# card.net
KiCad netlist of a schematic drawn in EAGLE
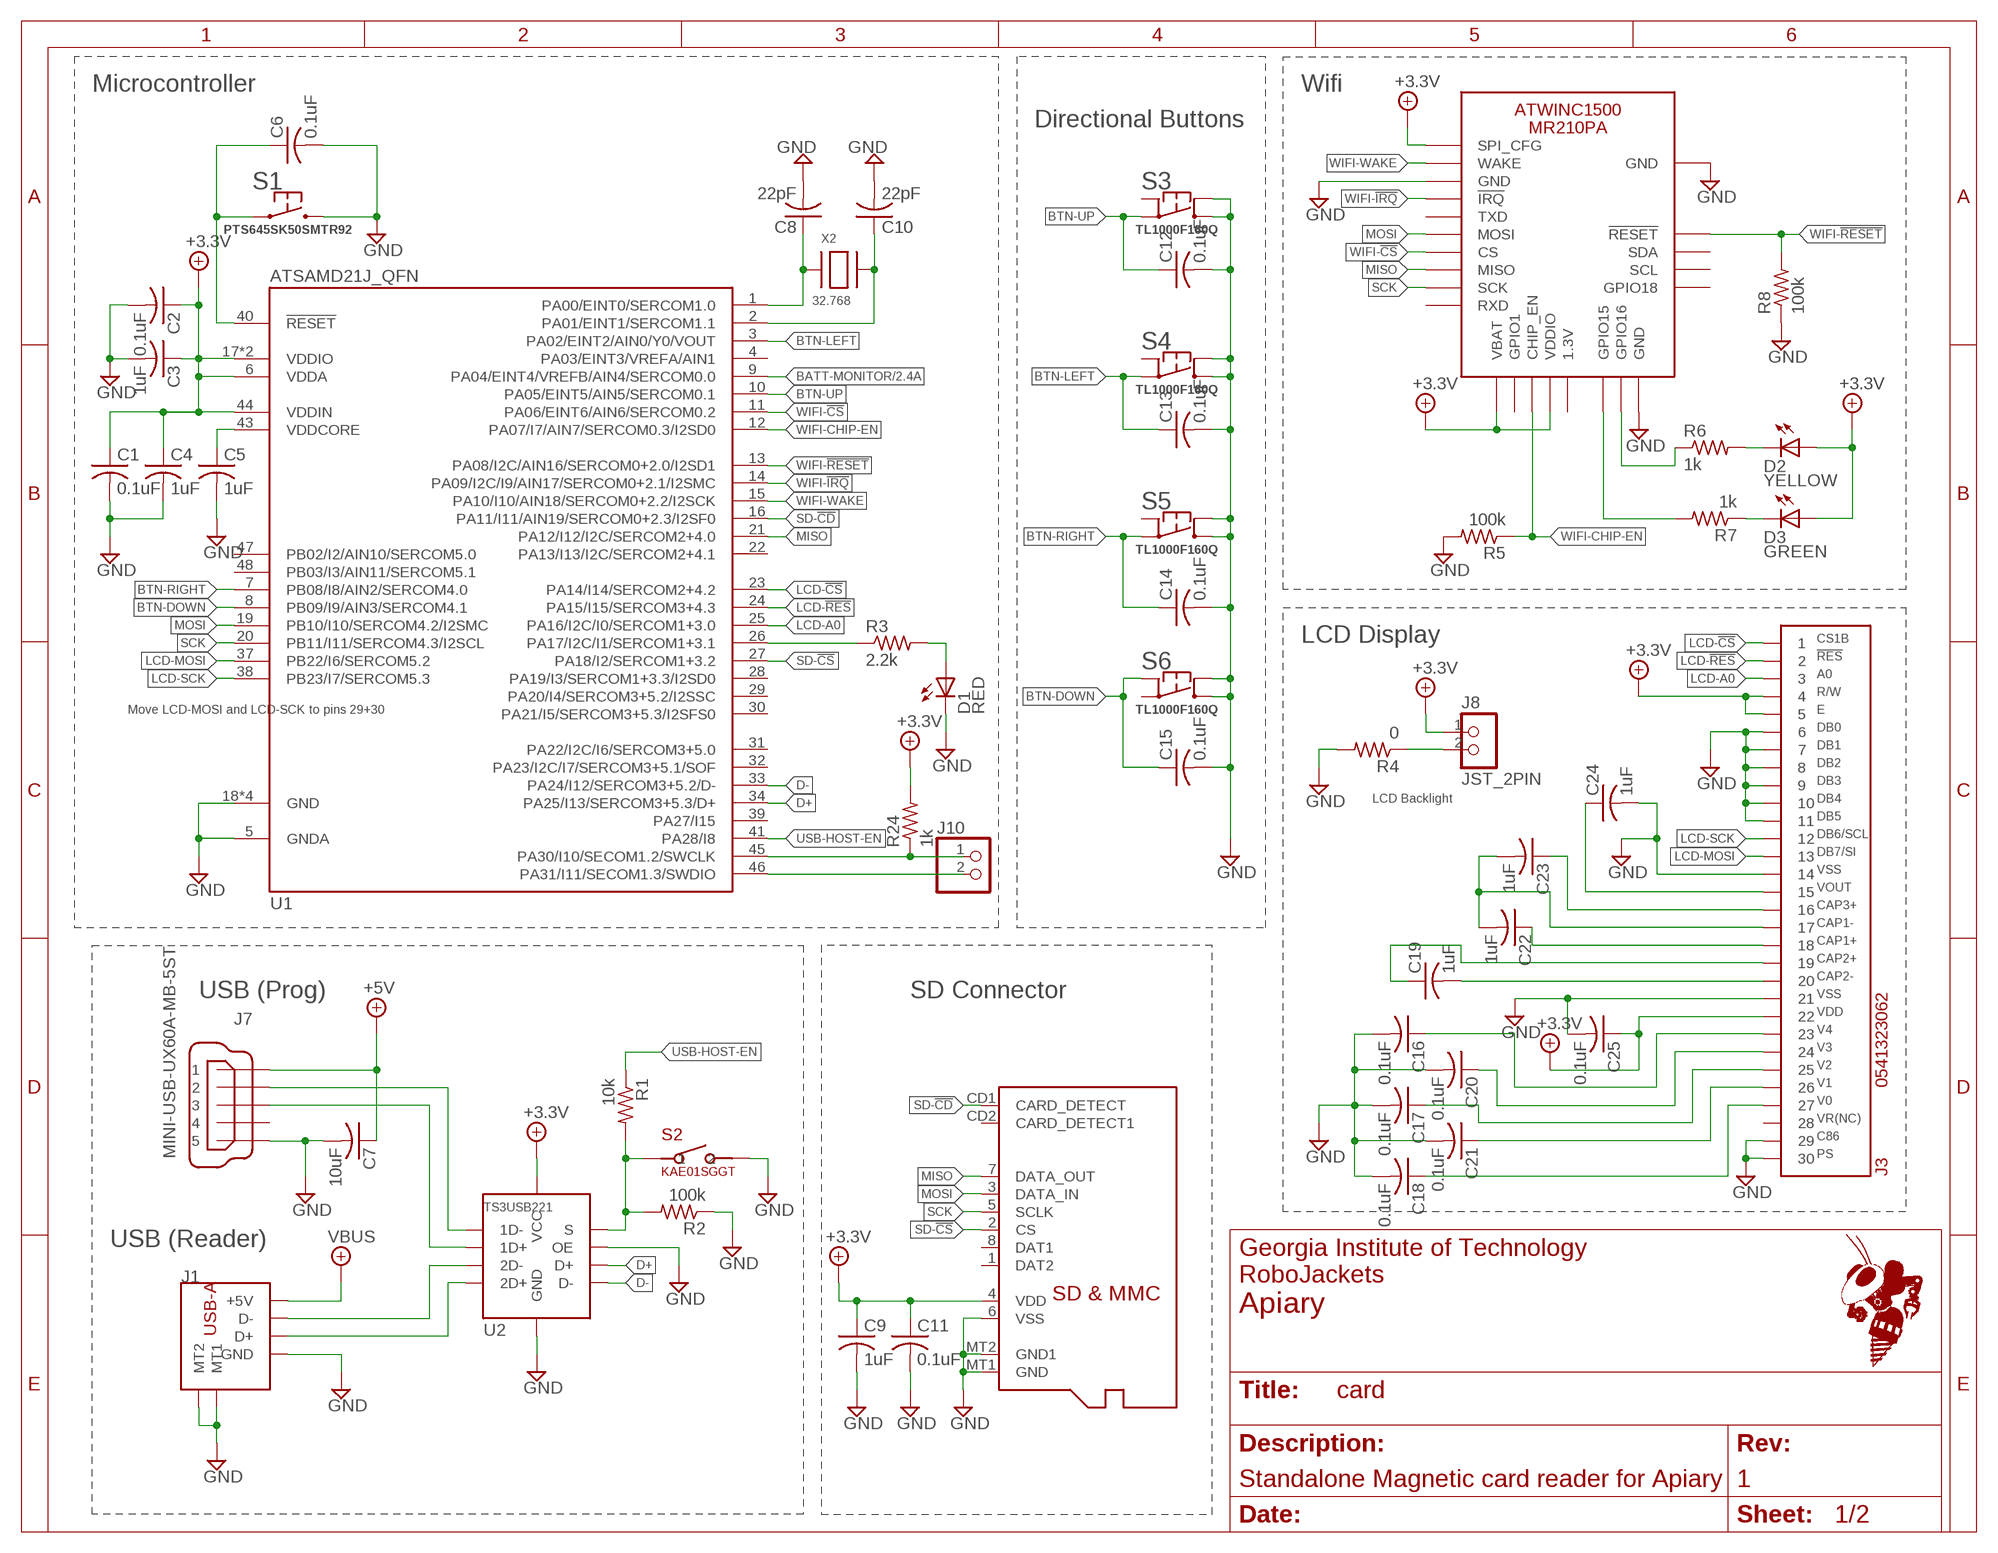
[diagram p0: schematic, sheet 1]
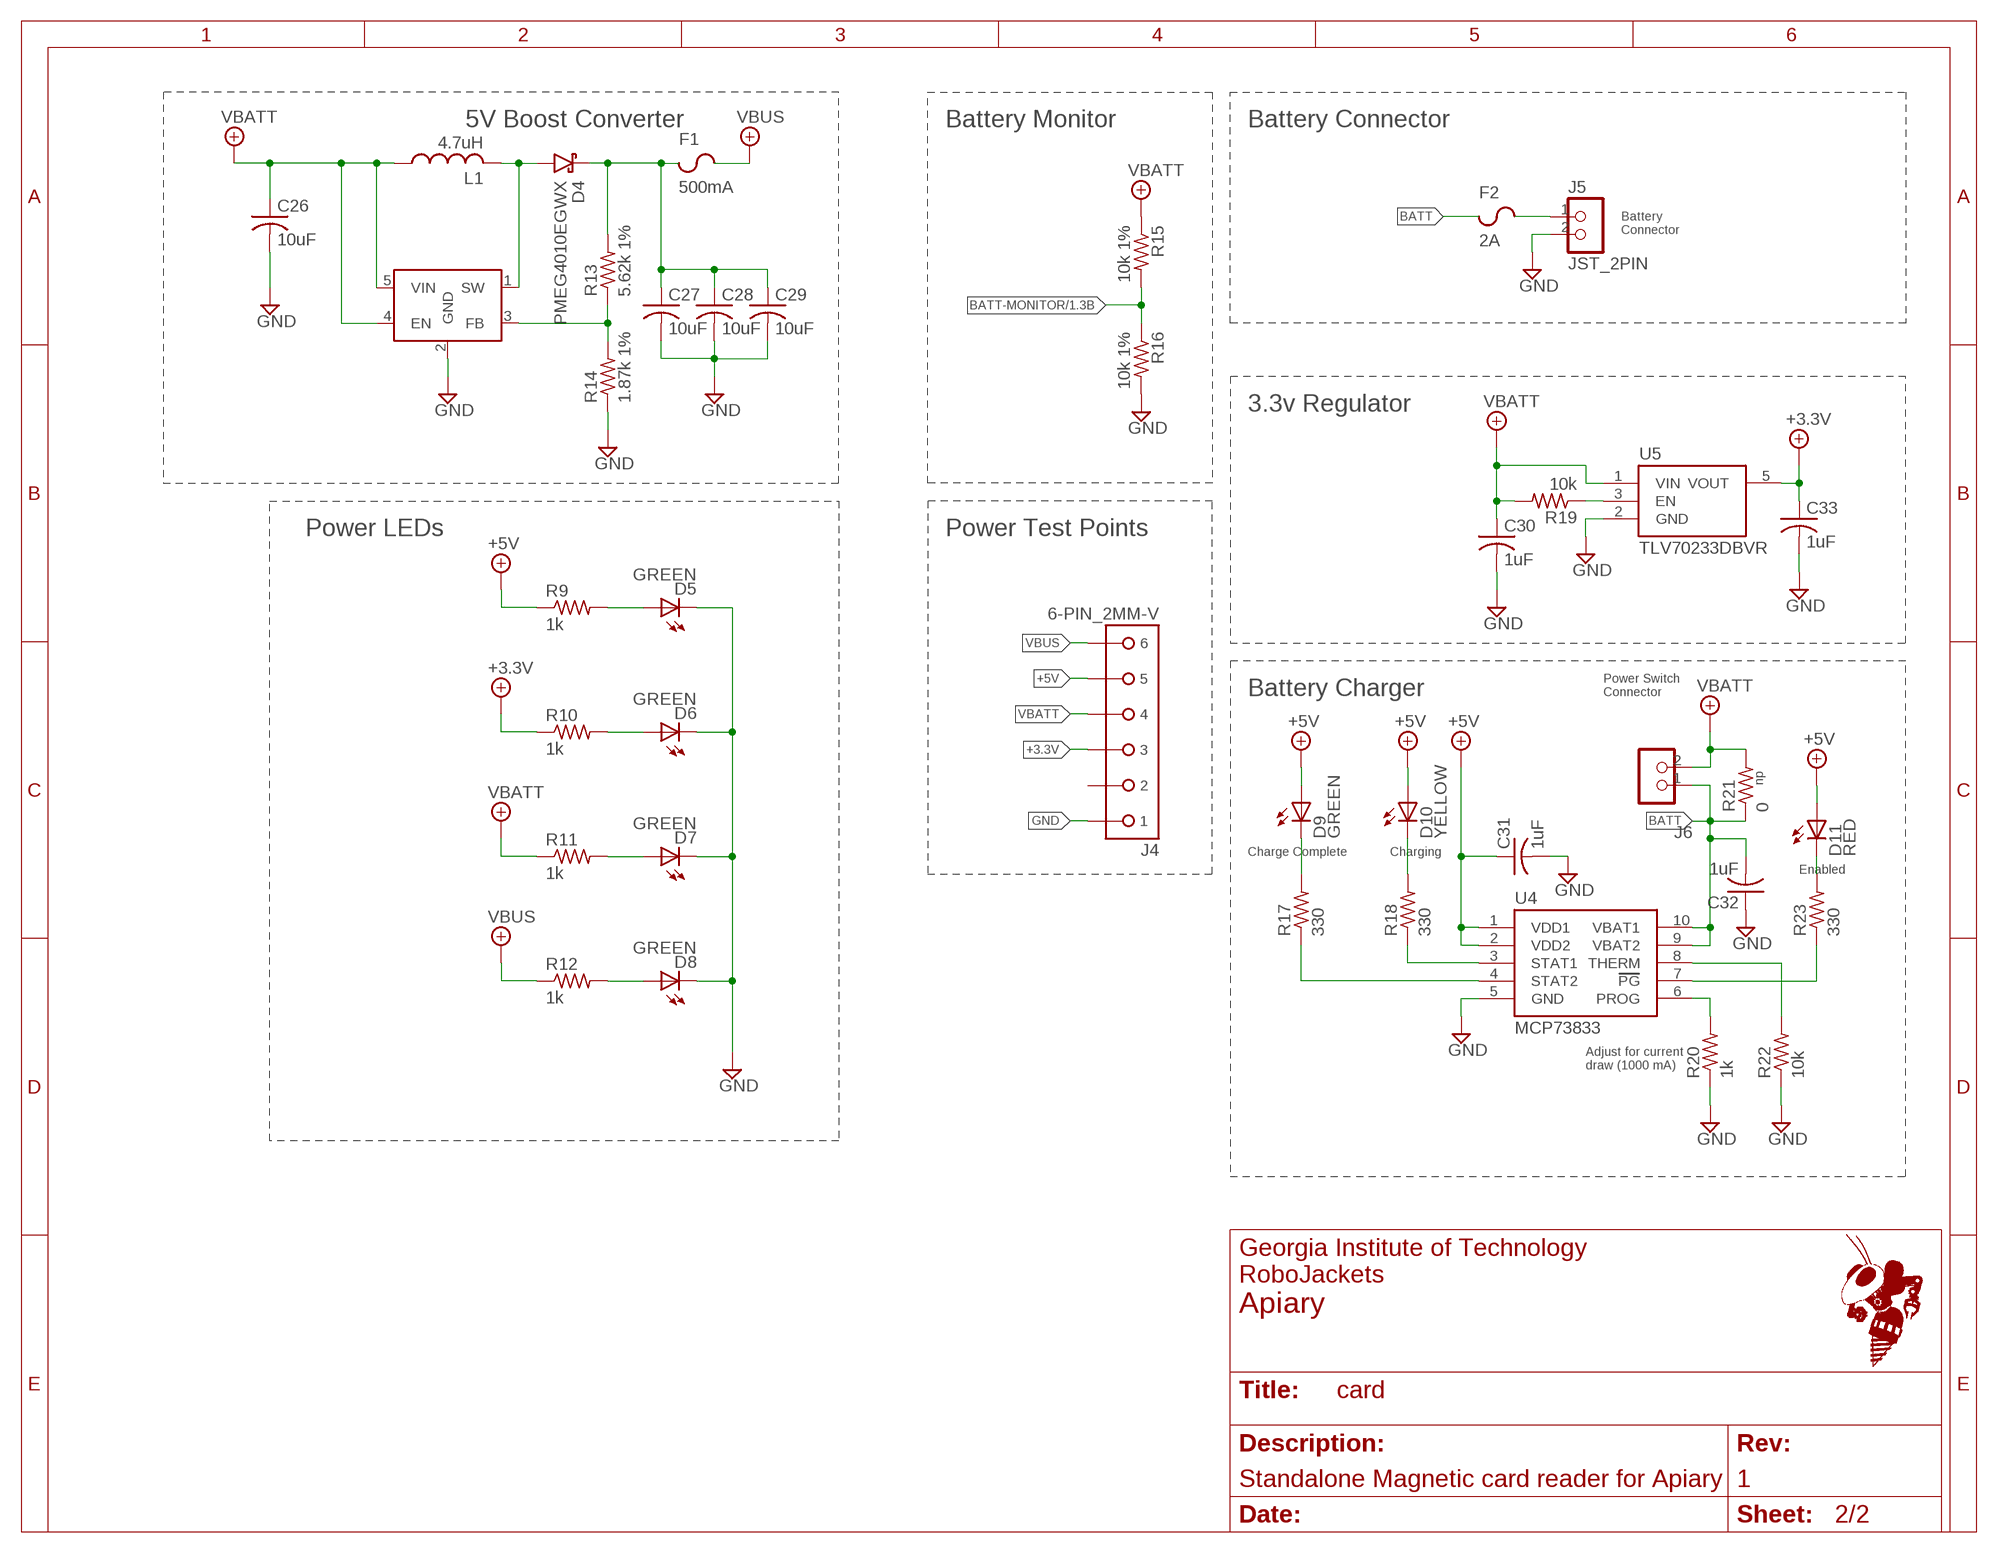
[diagram p1: schematic, sheet 2]

(export (version "E")
  (design (tool "Eeschema 10.0.6"))
  (components
    (comp (ref "C1")
      (value "0.1uF")
      (footprint "eagle-import:C0603")
      (libsource (lib "eagle-import") (part "rcl_334_C-USC0603"))
    )
    (comp (ref "C2")
      (value "0.1uF")
      (footprint "eagle-import:C0603")
      (libsource (lib "eagle-import") (part "rcl_334_C-USC0603"))
    )
    (comp (ref "C3")
      (value "1uF")
      (footprint "eagle-import:C0603")
      (libsource (lib "eagle-import") (part "rcl_334_C-USC0603"))
    )
    (comp (ref "C4")
      (value "1uF")
      (footprint "eagle-import:C0603")
      (libsource (lib "eagle-import") (part "rcl_334_C-USC0603"))
    )
    (comp (ref "C5")
      (value "1uF")
      (footprint "eagle-import:C0603")
      (libsource (lib "eagle-import") (part "rcl_334_C-USC0603"))
    )
    (comp (ref "C6")
      (value "0.1uF")
      (footprint "eagle-import:C0603")
      (libsource (lib "eagle-import") (part "rcl_334_C-USC0603"))
    )
    (comp (ref "C7")
      (value "10uF")
      (footprint "eagle-import:C0603")
      (libsource (lib "eagle-import") (part "C-USC0603"))
    )
    (comp (ref "C8")
      (value "22pF")
      (footprint "eagle-import:C0603")
      (libsource (lib "eagle-import") (part "rcl_334_C-USC0603"))
    )
    (comp (ref "C9")
      (value "1uF")
      (footprint "eagle-import:C0603")
      (libsource (lib "eagle-import") (part "rcl_334_C-USC0603"))
    )
    (comp (ref "C10")
      (value "22pF")
      (footprint "eagle-import:C0603")
      (libsource (lib "eagle-import") (part "rcl_334_C-USC0603"))
    )
    (comp (ref "C11")
      (value "0.1uF")
      (footprint "eagle-import:C0603")
      (libsource (lib "eagle-import") (part "rcl_334_C-USC0603"))
    )
    (comp (ref "C12")
      (value "0.1uF")
      (footprint "eagle-import:C0603")
      (libsource (lib "eagle-import") (part "rcl_334_C-USC0603"))
    )
    (comp (ref "C13")
      (value "0.1uF")
      (footprint "eagle-import:C0603")
      (libsource (lib "eagle-import") (part "rcl_334_C-USC0603"))
    )
    (comp (ref "C14")
      (value "0.1uF")
      (footprint "eagle-import:C0603")
      (libsource (lib "eagle-import") (part "rcl_334_C-USC0603"))
    )
    (comp (ref "C15")
      (value "0.1uF")
      (footprint "eagle-import:C0603")
      (libsource (lib "eagle-import") (part "rcl_334_C-USC0603"))
    )
    (comp (ref "C16")
      (value "0.1uF")
      (footprint "eagle-import:C0603")
      (libsource (lib "eagle-import") (part "rcl_334_C-USC0603"))
    )
    (comp (ref "C17")
      (value "0.1uF")
      (footprint "eagle-import:C0603")
      (libsource (lib "eagle-import") (part "rcl_334_C-USC0603"))
    )
    (comp (ref "C18")
      (value "0.1uF")
      (footprint "eagle-import:C0603")
      (libsource (lib "eagle-import") (part "rcl_334_C-USC0603"))
    )
    (comp (ref "C19")
      (value "1uF")
      (footprint "eagle-import:C0603")
      (libsource (lib "eagle-import") (part "rcl_334_C-USC0603"))
    )
    (comp (ref "C20")
      (value "0.1uF")
      (footprint "eagle-import:C0603")
      (libsource (lib "eagle-import") (part "rcl_334_C-USC0603"))
    )
    (comp (ref "C21")
      (value "0.1uF")
      (footprint "eagle-import:C0603")
      (libsource (lib "eagle-import") (part "rcl_334_C-USC0603"))
    )
    (comp (ref "C22")
      (value "1uF")
      (footprint "eagle-import:C0603")
      (libsource (lib "eagle-import") (part "rcl_334_C-USC0603"))
    )
    (comp (ref "C23")
      (value "1uF")
      (footprint "eagle-import:C0603")
      (libsource (lib "eagle-import") (part "rcl_334_C-USC0603"))
    )
    (comp (ref "C24")
      (value "1uF")
      (footprint "eagle-import:C0603")
      (libsource (lib "eagle-import") (part "rcl_334_C-USC0603"))
    )
    (comp (ref "C25")
      (value "0.1uF")
      (footprint "eagle-import:C0603")
      (libsource (lib "eagle-import") (part "rcl_334_C-USC0603"))
    )
    (comp (ref "D1")
      (value "RED")
      (footprint "eagle-import:CHIP-LED0603")
      (fields (field (name "MPN") "LTST-C191KRKT"))
      (libsource (lib "eagle-import") (part "LED-SMD-RED"))
    )
    (comp (ref "D2")
      (value "YELLOW")
      (footprint "eagle-import:CHIP-LED0603")
      (fields (field (name "MPN") "LTST-C191KSKT"))
      (libsource (lib "eagle-import") (part "LED-SMD-YELLOW"))
    )
    (comp (ref "D3")
      (value "GREEN")
      (footprint "eagle-import:CHIP-LED0603")
      (fields (field (name "MPN") "LTST-C191KGKT"))
      (libsource (lib "eagle-import") (part "LED-SMD-GREEN"))
    )
    (comp (ref "J1")
      (value "UE27AC54100")
      (footprint "eagle-import:USB-A")
      (libsource (lib "eagle-import") (part "UE27AC54100"))
    )
    (comp (ref "J2")
      (value "MICROSD")
      (footprint "eagle-import:MICROSD")
      (libsource (lib "eagle-import") (part "MICROSD"))
    )
    (comp (ref "J3")
      (value "0541323062")
      (footprint "eagle-import:0541323062")
      (libsource (lib "eagle-import") (part "0541323062"))
    )
    (comp (ref "J7")
      (value "MINI-USB-UX60A-MB-5ST")
      (footprint "eagle-import:UX60A-MB-5ST")
      (libsource (lib "eagle-import") (part "MINI-USB-UX60A-MB-5ST"))
    )
    (comp (ref "J8")
      (value "JST_2PIN")
      (footprint "eagle-import:JSTPH2")
      (libsource (lib "eagle-import") (part "card_JST_2PIN"))
    )
    (comp (ref "J10")
      (value "CONN-2VERT")
      (footprint "eagle-import:1X2")
      (libsource (lib "eagle-import") (part "CONN-2VERT"))
    )
    (comp (ref "R1")
      (value "10k")
      (footprint "eagle-import:R0603")
      (libsource (lib "eagle-import") (part "R-US_R0603"))
    )
    (comp (ref "R2")
      (value "100k")
      (footprint "eagle-import:R0603")
      (libsource (lib "eagle-import") (part "R-US_R0603"))
    )
    (comp (ref "R3")
      (value "2.2k")
      (footprint "eagle-import:R0603")
      (libsource (lib "eagle-import") (part "R-US_R0603"))
    )
    (comp (ref "R4")
      (value "0")
      (footprint "eagle-import:R0603")
      (libsource (lib "eagle-import") (part "R-US_R0603"))
    )
    (comp (ref "R5")
      (value "100k")
      (footprint "eagle-import:R0603")
      (libsource (lib "eagle-import") (part "R-US_R0603"))
    )
    (comp (ref "R6")
      (value "1k")
      (footprint "eagle-import:R0603")
      (libsource (lib "eagle-import") (part "R-US_R0603"))
    )
    (comp (ref "R7")
      (value "1k")
      (footprint "eagle-import:R0603")
      (libsource (lib "eagle-import") (part "R-US_R0603"))
    )
    (comp (ref "R8")
      (value "100k")
      (footprint "eagle-import:R0603")
      (libsource (lib "eagle-import") (part "R-US_R0603"))
    )
    (comp (ref "R24")
      (value "1k")
      (footprint "eagle-import:R0603")
      (libsource (lib "eagle-import") (part "R-US_R0603"))
    )
    (comp (ref "S1")
      (value "PTS645SK50SMTR92")
      (footprint "eagle-import:PTS645SK50SMTR92")
      (libsource (lib "eagle-import") (part "PTS645SK50SMTR92"))
    )
    (comp (ref "S2")
      (value "KAE01SGGT")
      (footprint "eagle-import:KAE01SGGT")
      (libsource (lib "eagle-import") (part "KAE01SGGT"))
    )
    (comp (ref "S3")
      (value "TL1000F160Q")
      (footprint "eagle-import:TL1100")
      (libsource (lib "eagle-import") (part "TL1000F160Q"))
    )
    (comp (ref "S4")
      (value "TL1000F160Q")
      (footprint "eagle-import:TL1100")
      (libsource (lib "eagle-import") (part "TL1000F160Q"))
    )
    (comp (ref "S5")
      (value "TL1000F160Q")
      (footprint "eagle-import:TL1100")
      (libsource (lib "eagle-import") (part "TL1000F160Q"))
    )
    (comp (ref "S6")
      (value "TL1000F160Q")
      (footprint "eagle-import:TL1100")
      (libsource (lib "eagle-import") (part "TL1000F160Q"))
    )
    (comp (ref "U1")
      (value "ATSAMD21J_QFN")
      (footprint "eagle-import:TQFN48_7MM")
      (libsource (lib "eagle-import") (part "ATSAMD21J_QFN"))
    )
    (comp (ref "U2")
      (value "TS3USB221")
      (footprint "eagle-import:10-PIN-UQFN")
      (libsource (lib "eagle-import") (part "TS3USB221"))
    )
    (comp (ref "X2")
      (value "32.768")
      (footprint "eagle-import:XTAL3215")
      (libsource (lib "eagle-import") (part "XTAL-3.2X1.5"))
    )
    (comp (ref "X3")
      (value "ATWINC1500_MR210PA")
      (footprint "eagle-import:ATWINC1500_MR210PA")
      (libsource (lib "eagle-import") (part "ATWINC1500_MR210PA"))
    )
    (comp (ref "C26")
      (value "10uF")
      (footprint "eagle-import:C0603")
      (libsource (lib "eagle-import") (part "rcl_334_C-USC0603"))
    )
    (comp (ref "C27")
      (value "10uF")
      (footprint "eagle-import:C0603")
      (libsource (lib "eagle-import") (part "rcl_334_C-USC0603"))
    )
    (comp (ref "C28")
      (value "10uF")
      (footprint "eagle-import:C0603")
      (libsource (lib "eagle-import") (part "rcl_334_C-USC0603"))
    )
    (comp (ref "C29")
      (value "10uF")
      (footprint "eagle-import:C0603")
      (libsource (lib "eagle-import") (part "rcl_334_C-USC0603"))
    )
    (comp (ref "C30")
      (value "1uF")
      (footprint "eagle-import:C0603")
      (libsource (lib "eagle-import") (part "rcl_334_C-USC0603"))
    )
    (comp (ref "C31")
      (value "1uF")
      (footprint "eagle-import:C0603")
      (libsource (lib "eagle-import") (part "rcl_334_C-USC0603"))
    )
    (comp (ref "C32")
      (value "1uF")
      (footprint "eagle-import:C0603")
      (libsource (lib "eagle-import") (part "rcl_334_C-USC0603"))
    )
    (comp (ref "C33")
      (value "1uF")
      (footprint "eagle-import:C0603")
      (libsource (lib "eagle-import") (part "rcl_334_C-USC0603"))
    )
    (comp (ref "D4")
      (value "PMEG4010EGWX")
      (footprint "eagle-import:SOD123")
      (libsource (lib "eagle-import") (part "SCHOTTKEY-DIODE-SOD123"))
    )
    (comp (ref "D5")
      (value "GREEN")
      (footprint "eagle-import:CHIP-LED0603")
      (fields (field (name "MPN") "LTST-C191KGKT"))
      (libsource (lib "eagle-import") (part "LED-SMD-GREEN"))
    )
    (comp (ref "D6")
      (value "GREEN")
      (footprint "eagle-import:CHIP-LED0603")
      (fields (field (name "MPN") "LTST-C191KGKT"))
      (libsource (lib "eagle-import") (part "LED-SMD-GREEN"))
    )
    (comp (ref "D7")
      (value "GREEN")
      (footprint "eagle-import:CHIP-LED0603")
      (fields (field (name "MPN") "LTST-C191KGKT"))
      (libsource (lib "eagle-import") (part "LED-SMD-GREEN"))
    )
    (comp (ref "D8")
      (value "GREEN")
      (footprint "eagle-import:CHIP-LED0603")
      (fields (field (name "MPN") "LTST-C191KGKT"))
      (libsource (lib "eagle-import") (part "LED-SMD-GREEN"))
    )
    (comp (ref "D9")
      (value "GREEN")
      (footprint "eagle-import:CHIP-LED0603")
      (fields (field (name "MPN") "LTST-C191KGKT"))
      (libsource (lib "eagle-import") (part "LED-SMD-GREEN"))
    )
    (comp (ref "D10")
      (value "YELLOW")
      (footprint "eagle-import:CHIP-LED0603")
      (fields (field (name "MPN") "LTST-C191KSKT"))
      (libsource (lib "eagle-import") (part "LED-SMD-YELLOW"))
    )
    (comp (ref "D11")
      (value "RED")
      (footprint "eagle-import:CHIP-LED0603")
      (fields (field (name "MPN") "LTST-C191KRKT"))
      (libsource (lib "eagle-import") (part "LED-SMD-RED"))
    )
    (comp (ref "F1")
      (value "500mA")
      (footprint "eagle-import:F0603")
      (libsource (lib "eagle-import") (part "CHIP_FUSE0603"))
    )
    (comp (ref "F2")
      (value "2A")
      (footprint "eagle-import:F0603")
      (libsource (lib "eagle-import") (part "CHIP_FUSE0603"))
    )
    (comp (ref "J4")
      (value "6-PIN_2MM-V")
      (footprint "eagle-import:2MM-6-V")
      (libsource (lib "eagle-import") (part "6-PIN_2MM-V"))
    )
    (comp (ref "J5")
      (value "JST_2PIN")
      (footprint "eagle-import:JSTPH2")
      (libsource (lib "eagle-import") (part "JST_2PIN"))
    )
    (comp (ref "J6")
      (value "JST_2PIN")
      (footprint "eagle-import:JSTPH2")
      (libsource (lib "eagle-import") (part "JST_2PIN"))
    )
    (comp (ref "L1")
      (value "4.7uH")
      (footprint "eagle-import:L0805")
      (libsource (lib "eagle-import") (part "L-US-0805"))
    )
    (comp (ref "R9")
      (value "1k")
      (footprint "eagle-import:R0603")
      (libsource (lib "eagle-import") (part "R-US_R0603"))
    )
    (comp (ref "R10")
      (value "1k")
      (footprint "eagle-import:R0603")
      (libsource (lib "eagle-import") (part "R-US_R0603"))
    )
    (comp (ref "R11")
      (value "1k")
      (footprint "eagle-import:R0603")
      (libsource (lib "eagle-import") (part "R-US_R0603"))
    )
    (comp (ref "R12")
      (value "1k")
      (footprint "eagle-import:R0603")
      (libsource (lib "eagle-import") (part "R-US_R0603"))
    )
    (comp (ref "R13")
      (value "5.62k 1%")
      (footprint "eagle-import:R0603")
      (libsource (lib "eagle-import") (part "R-US_R0603"))
    )
    (comp (ref "R14")
      (value "1.87k 1%")
      (footprint "eagle-import:R0603")
      (libsource (lib "eagle-import") (part "R-US_R0603"))
    )
    (comp (ref "R15")
      (value "10k 1%")
      (footprint "eagle-import:R0603")
      (libsource (lib "eagle-import") (part "R-US_R0603"))
    )
    (comp (ref "R16")
      (value "10k 1%")
      (footprint "eagle-import:R0603")
      (libsource (lib "eagle-import") (part "R-US_R0603"))
    )
    (comp (ref "R17")
      (value "330")
      (footprint "eagle-import:R0603")
      (libsource (lib "eagle-import") (part "R-US_R0603"))
    )
    (comp (ref "R18")
      (value "330")
      (footprint "eagle-import:R0603")
      (libsource (lib "eagle-import") (part "R-US_R0603"))
    )
    (comp (ref "R19")
      (value "10k")
      (footprint "eagle-import:R0603")
      (libsource (lib "eagle-import") (part "R-US_R0603"))
    )
    (comp (ref "R20")
      (value "1k")
      (footprint "eagle-import:R0603")
      (libsource (lib "eagle-import") (part "R-US_R0603"))
    )
    (comp (ref "R21")
      (value "0")
      (footprint "eagle-import:R0603")
      (libsource (lib "eagle-import") (part "R-US_R0603"))
    )
    (comp (ref "R22")
      (value "10k")
      (footprint "eagle-import:R0603")
      (libsource (lib "eagle-import") (part "R-US_R0603"))
    )
    (comp (ref "R23")
      (value "330")
      (footprint "eagle-import:R0603")
      (libsource (lib "eagle-import") (part "R-US_R0603"))
    )
    (comp (ref "U3")
      (value "MIC2288YD5-TR")
      (footprint "eagle-import:TSOT-23-5")
      (libsource (lib "eagle-import") (part "MIC2288YD5-TR"))
    )
    (comp (ref "U4")
      (value "MCP73833")
      (footprint "eagle-import:MSOP10")
      (libsource (lib "eagle-import") (part "MCP73833"))
    )
    (comp (ref "U5")
      (value "TLV70233DBVR")
      (footprint "eagle-import:SOT-23-5")
      (libsource (lib "eagle-import") (part "TLV70233DBVR"))
    )
  )
  (nets
    (net (code "1") (name "+3.3V") (class "Default")
      (node (ref "C1") (pin "1") (pinfunction "1_1") (pintype "passive"))
      (node (ref "C11") (pin "1") (pinfunction "1_1") (pintype "passive"))
      (node (ref "C2") (pin "1") (pinfunction "1_1") (pintype "passive"))
      (node (ref "C25") (pin "1") (pinfunction "1_1") (pintype "passive"))
      (node (ref "C3") (pin "1") (pinfunction "1_1") (pintype "passive"))
      (node (ref "C33") (pin "1") (pinfunction "1_1") (pintype "passive"))
      (node (ref "C4") (pin "1") (pinfunction "1_1") (pintype "passive"))
      (node (ref "C9") (pin "1") (pinfunction "1_1") (pintype "passive"))
      (node (ref "D2") (pin "A") (pinfunction "A_A") (pintype "passive"))
      (node (ref "D3") (pin "A") (pinfunction "A_A") (pintype "passive"))
      (node (ref "J2") (pin "4") (pinfunction "VDD_4") (pintype "bidirectional"))
      (node (ref "J3") (pin "22") (pinfunction "22_22") (pintype "bidirectional"))
      (node (ref "J3") (pin "4") (pinfunction "4_4") (pintype "bidirectional"))
      (node (ref "J3") (pin "5") (pinfunction "5_5") (pintype "bidirectional"))
      (node (ref "J4") (pin "3") (pinfunction "3_3") (pintype "passive"))
      (node (ref "J8") (pin "1") (pinfunction "1_1") (pintype "bidirectional"))
      (node (ref "R10") (pin "1") (pinfunction "1_1") (pintype "passive"))
      (node (ref "R24") (pin "2") (pinfunction "2_2") (pintype "passive"))
      (node (ref "U1") (pin "17") (pinfunction "VDDIO_17") (pintype "bidirectional"))
      (node (ref "U1") (pin "36") (pinfunction "VDDIO_36") (pintype "bidirectional"))
      (node (ref "U1") (pin "44") (pinfunction "VDDIN_44") (pintype "bidirectional"))
      (node (ref "U1") (pin "6") (pinfunction "VDDA_6") (pintype "bidirectional"))
      (node (ref "U2") (pin "10") (pinfunction "VCC_10") (pintype "bidirectional"))
      (node (ref "U5") (pin "5") (pinfunction "VOUT_5") (pintype "bidirectional"))
      (node (ref "X3") (pin "J10") (pinfunction "SPI_CFG_J10") (pintype "bidirectional"))
      (node (ref "X3") (pin "J20") (pinfunction "VBAT_J20") (pintype "bidirectional"))
      (node (ref "X3") (pin "J23") (pinfunction "VDDIO_J23") (pintype "bidirectional"))
    )
    (net (code "2") (name "+5V") (class "Default")
      (node (ref "C31") (pin "1") (pinfunction "1_1") (pintype "passive"))
      (node (ref "C7") (pin "1") (pinfunction "1_1") (pintype "passive"))
      (node (ref "D10") (pin "A") (pinfunction "A_A") (pintype "passive"))
      (node (ref "D11") (pin "A") (pinfunction "A_A") (pintype "passive"))
      (node (ref "D9") (pin "A") (pinfunction "A_A") (pintype "passive"))
      (node (ref "J4") (pin "5") (pinfunction "5_5") (pintype "passive"))
      (node (ref "J7") (pin "1") (pinfunction "1_1") (pintype "input"))
      (node (ref "R9") (pin "1") (pinfunction "1_1") (pintype "passive"))
      (node (ref "U4") (pin "1") (pinfunction "VDD1_1") (pintype "bidirectional"))
      (node (ref "U4") (pin "2") (pinfunction "VDD2_2") (pintype "bidirectional"))
    )
    (net (code "3") (name "BATT") (class "Default")
      (node (ref "C32") (pin "2") (pinfunction "2_2") (pintype "passive"))
      (node (ref "F2") (pin "1") (pinfunction "1_1") (pintype "bidirectional"))
      (node (ref "J6") (pin "1") (pinfunction "1_1") (pintype "bidirectional"))
      (node (ref "R21") (pin "1") (pinfunction "1_1") (pintype "passive"))
      (node (ref "U4") (pin "10") (pinfunction "VBAT1_10") (pintype "bidirectional"))
      (node (ref "U4") (pin "9") (pinfunction "VBAT2_9") (pintype "bidirectional"))
    )
    (net (code "4") (name "BATT-MONITOR") (class "Default")
      (node (ref "R15") (pin "2") (pinfunction "2_2") (pintype "passive"))
      (node (ref "R16") (pin "1") (pinfunction "1_1") (pintype "passive"))
      (node (ref "U1") (pin "9") (pinfunction "PA04/EINT4/VREFB/AIN4/SERCOM0.0_9") (pintype "bidirectional"))
    )
    (net (code "5") (name "BTN-DOWN") (class "Default")
      (node (ref "C15") (pin "1") (pinfunction "1_1") (pintype "passive"))
      (node (ref "S6") (pin "2") (pinfunction "1B_2") (pintype "passive"))
      (node (ref "U1") (pin "8") (pinfunction "PB09/I9/AIN3/SERCOM4.1_8") (pintype "bidirectional"))
    )
    (net (code "6") (name "BTN-LEFT") (class "Default")
      (node (ref "C13") (pin "1") (pinfunction "1_1") (pintype "passive"))
      (node (ref "S4") (pin "1") (pinfunction "1A_1") (pintype "passive"))
      (node (ref "U1") (pin "3") (pinfunction "PA02/EINT2/AIN0/Y0/VOUT_3") (pintype "bidirectional"))
    )
    (net (code "7") (name "BTN-RIGHT") (class "Default")
      (node (ref "C14") (pin "1") (pinfunction "1_1") (pintype "passive"))
      (node (ref "S5") (pin "1") (pinfunction "1A_1") (pintype "passive"))
      (node (ref "U1") (pin "7") (pinfunction "PB08/I8/AIN2/SERCOM4.0_7") (pintype "bidirectional"))
    )
    (net (code "8") (name "BTN-UP") (class "Default")
      (node (ref "C12") (pin "1") (pinfunction "1_1") (pintype "passive"))
      (node (ref "S3") (pin "1") (pinfunction "1A_1") (pintype "passive"))
      (node (ref "U1") (pin "10") (pinfunction "PA05/EINT5/AIN5/SERCOM0.1_10") (pintype "bidirectional"))
    )
    (net (code "9") (name "D+") (class "Default")
      (node (ref "U1") (pin "34") (pinfunction "PA25/I13/SERCOM3+5.3/D+_34") (pintype "bidirectional"))
      (node (ref "U2") (pin "8") (pinfunction "D+_8") (pintype "bidirectional"))
    )
    (net (code "10") (name "D-") (class "Default")
      (node (ref "U1") (pin "33") (pinfunction "PA24/I12/SERCOM3+5.2/D-_33") (pintype "bidirectional"))
      (node (ref "U2") (pin "7") (pinfunction "D-_7") (pintype "bidirectional"))
    )
    (net (code "11") (name "GND") (class "Default")
      (node (ref "C1") (pin "2") (pinfunction "2_2") (pintype "passive"))
      (node (ref "C10") (pin "2") (pinfunction "2_2") (pintype "passive"))
      (node (ref "C11") (pin "2") (pinfunction "2_2") (pintype "passive"))
      (node (ref "C12") (pin "2") (pinfunction "2_2") (pintype "passive"))
      (node (ref "C13") (pin "2") (pinfunction "2_2") (pintype "passive"))
      (node (ref "C14") (pin "2") (pinfunction "2_2") (pintype "passive"))
      (node (ref "C15") (pin "2") (pinfunction "2_2") (pintype "passive"))
      (node (ref "C16") (pin "2") (pinfunction "2_2") (pintype "passive"))
      (node (ref "C17") (pin "2") (pinfunction "2_2") (pintype "passive"))
      (node (ref "C18") (pin "2") (pinfunction "2_2") (pintype "passive"))
      (node (ref "C2") (pin "2") (pinfunction "2_2") (pintype "passive"))
      (node (ref "C20") (pin "2") (pinfunction "2_2") (pintype "passive"))
      (node (ref "C21") (pin "2") (pinfunction "2_2") (pintype "passive"))
      (node (ref "C24") (pin "2") (pinfunction "2_2") (pintype "passive"))
      (node (ref "C25") (pin "2") (pinfunction "2_2") (pintype "passive"))
      (node (ref "C26") (pin "2") (pinfunction "2_2") (pintype "passive"))
      (node (ref "C27") (pin "2") (pinfunction "2_2") (pintype "passive"))
      (node (ref "C28") (pin "2") (pinfunction "2_2") (pintype "passive"))
      (node (ref "C29") (pin "2") (pinfunction "2_2") (pintype "passive"))
      (node (ref "C3") (pin "2") (pinfunction "2_2") (pintype "passive"))
      (node (ref "C30") (pin "2") (pinfunction "2_2") (pintype "passive"))
      (node (ref "C31") (pin "2") (pinfunction "2_2") (pintype "passive"))
      (node (ref "C32") (pin "1") (pinfunction "1_1") (pintype "passive"))
      (node (ref "C33") (pin "2") (pinfunction "2_2") (pintype "passive"))
      (node (ref "C4") (pin "2") (pinfunction "2_2") (pintype "passive"))
      (node (ref "C5") (pin "2") (pinfunction "2_2") (pintype "passive"))
      (node (ref "C6") (pin "2") (pinfunction "2_2") (pintype "passive"))
      (node (ref "C7") (pin "2") (pinfunction "2_2") (pintype "passive"))
      (node (ref "C8") (pin "2") (pinfunction "2_2") (pintype "passive"))
      (node (ref "C9") (pin "2") (pinfunction "2_2") (pintype "passive"))
      (node (ref "D1") (pin "C") (pinfunction "K_C") (pintype "passive"))
      (node (ref "D5") (pin "C") (pinfunction "K_C") (pintype "passive"))
      (node (ref "D6") (pin "C") (pinfunction "K_C") (pintype "passive"))
      (node (ref "D7") (pin "C") (pinfunction "K_C") (pintype "passive"))
      (node (ref "D8") (pin "C") (pinfunction "K_C") (pintype "passive"))
      (node (ref "J1") (pin "4") (pinfunction "GND_4") (pintype "bidirectional"))
      (node (ref "J1") (pin "MT1") (pinfunction "MT1_MT1") (pintype "bidirectional"))
      (node (ref "J1") (pin "MT2") (pinfunction "MT2_MT2") (pintype "bidirectional"))
      (node (ref "J2") (pin "6") (pinfunction "VSS_6") (pintype "bidirectional"))
      (node (ref "J2") (pin "MT1") (pinfunction "GND_MT1") (pintype "bidirectional"))
      (node (ref "J2") (pin "MT2") (pinfunction "GND1_MT2") (pintype "bidirectional"))
      (node (ref "J3") (pin "10") (pinfunction "10_10") (pintype "bidirectional"))
      (node (ref "J3") (pin "11") (pinfunction "11_11") (pintype "bidirectional"))
      (node (ref "J3") (pin "14") (pinfunction "14_14") (pintype "bidirectional"))
      (node (ref "J3") (pin "21") (pinfunction "21_21") (pintype "bidirectional"))
      (node (ref "J3") (pin "29") (pinfunction "29_29") (pintype "bidirectional"))
      (node (ref "J3") (pin "30") (pinfunction "30_30") (pintype "bidirectional"))
      (node (ref "J3") (pin "6") (pinfunction "6_6") (pintype "bidirectional"))
      (node (ref "J3") (pin "7") (pinfunction "7_7") (pintype "bidirectional"))
      (node (ref "J3") (pin "8") (pinfunction "8_8") (pintype "bidirectional"))
      (node (ref "J3") (pin "9") (pinfunction "9_9") (pintype "bidirectional"))
      (node (ref "J4") (pin "1") (pinfunction "1_1") (pintype "passive"))
      (node (ref "J5") (pin "2") (pinfunction "2_2") (pintype "bidirectional"))
      (node (ref "J7") (pin "5") (pinfunction "5_5") (pintype "input"))
      (node (ref "R14") (pin "1") (pinfunction "1_1") (pintype "passive"))
      (node (ref "R16") (pin "2") (pinfunction "2_2") (pintype "passive"))
      (node (ref "R2") (pin "1") (pinfunction "1_1") (pintype "passive"))
      (node (ref "R20") (pin "1") (pinfunction "1_1") (pintype "passive"))
      (node (ref "R22") (pin "1") (pinfunction "1_1") (pintype "passive"))
      (node (ref "R4") (pin "2") (pinfunction "2_2") (pintype "passive"))
      (node (ref "R5") (pin "2") (pinfunction "2_2") (pintype "passive"))
      (node (ref "R8") (pin "1") (pinfunction "1_1") (pintype "passive"))
      (node (ref "S1") (pin "3") (pinfunction "2_3") (pintype "passive"))
      (node (ref "S1") (pin "4") (pinfunction "2_4") (pintype "passive"))
      (node (ref "S2") (pin "2") (pinfunction "2_2") (pintype "passive"))
      (node (ref "S3") (pin "3") (pinfunction "2A_3") (pintype "passive"))
      (node (ref "S3") (pin "4") (pinfunction "2B_4") (pintype "passive"))
      (node (ref "S4") (pin "3") (pinfunction "2A_3") (pintype "passive"))
      (node (ref "S4") (pin "4") (pinfunction "2B_4") (pintype "passive"))
      (node (ref "S5") (pin "3") (pinfunction "2A_3") (pintype "passive"))
      (node (ref "S5") (pin "4") (pinfunction "2B_4") (pintype "passive"))
      (node (ref "S6") (pin "3") (pinfunction "2A_3") (pintype "passive"))
      (node (ref "S6") (pin "4") (pinfunction "2B_4") (pintype "passive"))
      (node (ref "U1") (pin "18") (pinfunction "GND_18") (pintype "bidirectional"))
      (node (ref "U1") (pin "35") (pinfunction "GND_35") (pintype "bidirectional"))
      (node (ref "U1") (pin "42") (pinfunction "GND_42") (pintype "bidirectional"))
      (node (ref "U1") (pin "5") (pinfunction "GNDA_5") (pintype "bidirectional"))
      (node (ref "U1") (pin "THERMAL") (pinfunction "GND_THERMAL") (pintype "bidirectional"))
      (node (ref "U2") (pin "5") (pinfunction "GND_5") (pintype "bidirectional"))
      (node (ref "U2") (pin "6") (pinfunction "OE_6") (pintype "bidirectional"))
      (node (ref "U3") (pin "2") (pinfunction "GND_2") (pintype "bidirectional"))
      (node (ref "U4") (pin "5") (pinfunction "GND_5") (pintype "bidirectional"))
      (node (ref "U5") (pin "2") (pinfunction "GND_2") (pintype "bidirectional"))
      (node (ref "X3") (pin "J12") (pinfunction "GND_J12") (pintype "bidirectional"))
      (node (ref "X3") (pin "J28") (pinfunction "GND_J28") (pintype "bidirectional"))
      (node (ref "X3") (pin "J9") (pinfunction "GND_J9") (pintype "bidirectional"))
    )
    (net (code "12") (name "LCD-A0") (class "Default")
      (node (ref "J3") (pin "3") (pinfunction "3_3") (pintype "bidirectional"))
      (node (ref "U1") (pin "25") (pinfunction "PA16/I2C/I0/SERCOM1+3.0_25") (pintype "bidirectional"))
    )
    (net (code "13") (name "LCD-MOSI") (class "Default")
      (node (ref "J3") (pin "13") (pinfunction "13_13") (pintype "bidirectional"))
      (node (ref "U1") (pin "37") (pinfunction "PB22/I6/SERCOM5.2_37") (pintype "bidirectional"))
    )
    (net (code "14") (name "LCD-SCK") (class "Default")
      (node (ref "J3") (pin "12") (pinfunction "12_12") (pintype "bidirectional"))
      (node (ref "U1") (pin "38") (pinfunction "PB23/I7/SERCOM5.3_38") (pintype "bidirectional"))
    )
    (net (code "15") (name "LCD-~{CS}") (class "Default")
      (node (ref "J3") (pin "1") (pinfunction "1_1") (pintype "bidirectional"))
      (node (ref "U1") (pin "23") (pinfunction "PA14/I14/SERCOM2+4.2_23") (pintype "bidirectional"))
    )
    (net (code "16") (name "LCD-~{RES}") (class "Default")
      (node (ref "J3") (pin "2") (pinfunction "2_2") (pintype "bidirectional"))
      (node (ref "U1") (pin "24") (pinfunction "PA15/I15/SERCOM3+4.3_24") (pintype "bidirectional"))
    )
    (net (code "17") (name "MISO") (class "Default")
      (node (ref "J2") (pin "7") (pinfunction "DATA_OUT_7") (pintype "bidirectional"))
      (node (ref "U1") (pin "21") (pinfunction "PA12/I12/I2C/SERCOM2+4.0_21") (pintype "bidirectional"))
      (node (ref "X3") (pin "J17") (pinfunction "MISO_J17") (pintype "bidirectional"))
    )
    (net (code "18") (name "MOSI") (class "Default")
      (node (ref "J2") (pin "3") (pinfunction "DATA_IN_3") (pintype "bidirectional"))
      (node (ref "U1") (pin "19") (pinfunction "PB10/I10/SERCOM4.2/I2SMC_19") (pintype "bidirectional"))
      (node (ref "X3") (pin "J15") (pinfunction "MOSI_J15") (pintype "input"))
    )
    (net (code "19") (name "Net-(C16-Pad1)") (class "Default")
      (node (ref "C16") (pin "1") (pinfunction "1_1") (pintype "passive"))
      (node (ref "J3") (pin "23") (pinfunction "23_23") (pintype "bidirectional"))
    )
    (net (code "20") (name "Net-(C17-Pad1)") (class "Default")
      (node (ref "C17") (pin "1") (pinfunction "1_1") (pintype "passive"))
      (node (ref "J3") (pin "25") (pinfunction "25_25") (pintype "bidirectional"))
    )
    (net (code "21") (name "Net-(C18-Pad1)") (class "Default")
      (node (ref "C18") (pin "1") (pinfunction "1_1") (pintype "passive"))
      (node (ref "J3") (pin "27") (pinfunction "27_27") (pintype "bidirectional"))
    )
    (net (code "22") (name "Net-(C19-Pad1)") (class "Default")
      (node (ref "C19") (pin "1") (pinfunction "1_1") (pintype "passive"))
      (node (ref "J3") (pin "19") (pinfunction "19_19") (pintype "bidirectional"))
    )
    (net (code "23") (name "Net-(C19-Pad2)") (class "Default")
      (node (ref "C19") (pin "2") (pinfunction "2_2") (pintype "passive"))
      (node (ref "J3") (pin "20") (pinfunction "20_20") (pintype "bidirectional"))
    )
    (net (code "24") (name "Net-(C20-Pad1)") (class "Default")
      (node (ref "C20") (pin "1") (pinfunction "1_1") (pintype "passive"))
      (node (ref "J3") (pin "24") (pinfunction "24_24") (pintype "bidirectional"))
    )
    (net (code "25") (name "Net-(C21-Pad1)") (class "Default")
      (node (ref "C21") (pin "1") (pinfunction "1_1") (pintype "passive"))
      (node (ref "J3") (pin "26") (pinfunction "26_26") (pintype "bidirectional"))
    )
    (net (code "26") (name "Net-(C22-Pad1)") (class "Default")
      (node (ref "C22") (pin "1") (pinfunction "1_1") (pintype "passive"))
      (node (ref "J3") (pin "18") (pinfunction "18_18") (pintype "bidirectional"))
    )
    (net (code "27") (name "Net-(C22-Pad2)") (class "Default")
      (node (ref "C22") (pin "2") (pinfunction "2_2") (pintype "passive"))
      (node (ref "C23") (pin "2") (pinfunction "2_2") (pintype "passive"))
      (node (ref "J3") (pin "17") (pinfunction "17_17") (pintype "bidirectional"))
    )
    (net (code "28") (name "Net-(C23-Pad1)") (class "Default")
      (node (ref "C23") (pin "1") (pinfunction "1_1") (pintype "passive"))
      (node (ref "J3") (pin "16") (pinfunction "16_16") (pintype "bidirectional"))
    )
    (net (code "29") (name "Net-(C24-Pad1)") (class "Default")
      (node (ref "C24") (pin "1") (pinfunction "1_1") (pintype "passive"))
      (node (ref "J3") (pin "15") (pinfunction "15_15") (pintype "bidirectional"))
    )
    (net (code "30") (name "Net-(C27-Pad1)") (class "Default")
      (node (ref "C27") (pin "1") (pinfunction "1_1") (pintype "passive"))
      (node (ref "C28") (pin "1") (pinfunction "1_1") (pintype "passive"))
      (node (ref "C29") (pin "1") (pinfunction "1_1") (pintype "passive"))
      (node (ref "D4") (pin "C") (pinfunction "C_C") (pintype "passive"))
      (node (ref "F1") (pin "1") (pinfunction "1_1") (pintype "bidirectional"))
      (node (ref "R13") (pin "2") (pinfunction "2_2") (pintype "passive"))
    )
    (net (code "31") (name "Net-(D1-PadA)") (class "Default")
      (node (ref "D1") (pin "A") (pinfunction "A_A") (pintype "passive"))
      (node (ref "R3") (pin "2") (pinfunction "2_2") (pintype "passive"))
    )
    (net (code "32") (name "Net-(D2-K)") (class "Default")
      (node (ref "D2") (pin "C") (pinfunction "K_C") (pintype "passive"))
      (node (ref "R6") (pin "2") (pinfunction "2_2") (pintype "passive"))
    )
    (net (code "33") (name "Net-(D3-K)") (class "Default")
      (node (ref "D3") (pin "C") (pinfunction "K_C") (pintype "passive"))
      (node (ref "R7") (pin "1") (pinfunction "1_1") (pintype "passive"))
    )
    (net (code "34") (name "Net-(D5-PadA)") (class "Default")
      (node (ref "D5") (pin "A") (pinfunction "A_A") (pintype "passive"))
      (node (ref "R9") (pin "2") (pinfunction "2_2") (pintype "passive"))
    )
    (net (code "35") (name "Net-(D6-PadA)") (class "Default")
      (node (ref "D6") (pin "A") (pinfunction "A_A") (pintype "passive"))
      (node (ref "R10") (pin "2") (pinfunction "2_2") (pintype "passive"))
    )
    (net (code "36") (name "Net-(D7-PadA)") (class "Default")
      (node (ref "D7") (pin "A") (pinfunction "A_A") (pintype "passive"))
      (node (ref "R11") (pin "2") (pinfunction "2_2") (pintype "passive"))
    )
    (net (code "37") (name "Net-(D8-PadA)") (class "Default")
      (node (ref "D8") (pin "A") (pinfunction "A_A") (pintype "passive"))
      (node (ref "R12") (pin "2") (pinfunction "2_2") (pintype "passive"))
    )
    (net (code "38") (name "Net-(D9-K)") (class "Default")
      (node (ref "D9") (pin "C") (pinfunction "K_C") (pintype "passive"))
      (node (ref "R17") (pin "2") (pinfunction "2_2") (pintype "passive"))
    )
    (net (code "39") (name "Net-(D10-K)") (class "Default")
      (node (ref "D10") (pin "C") (pinfunction "K_C") (pintype "passive"))
      (node (ref "R18") (pin "2") (pinfunction "2_2") (pintype "passive"))
    )
    (net (code "40") (name "Net-(D11-K)") (class "Default")
      (node (ref "D11") (pin "C") (pinfunction "K_C") (pintype "passive"))
      (node (ref "R23") (pin "2") (pinfunction "2_2") (pintype "passive"))
    )
    (net (code "41") (name "Net-(F2-Pad2)") (class "Default")
      (node (ref "F2") (pin "2") (pinfunction "2_2") (pintype "bidirectional"))
      (node (ref "J5") (pin "1") (pinfunction "1_1") (pintype "bidirectional"))
    )
    (net (code "42") (name "Net-(J1-D+)") (class "Default")
      (node (ref "J1") (pin "3") (pinfunction "D+_3") (pintype "bidirectional"))
      (node (ref "U2") (pin "3") (pinfunction "2D+_3") (pintype "bidirectional"))
    )
    (net (code "43") (name "Net-(J1-D-)") (class "Default")
      (node (ref "J1") (pin "2") (pinfunction "D-_2") (pintype "bidirectional"))
      (node (ref "U2") (pin "4") (pinfunction "2D-_4") (pintype "bidirectional"))
    )
    (net (code "44") (name "Net-(J8-Pad2)") (class "Default")
      (node (ref "J8") (pin "2") (pinfunction "2_2") (pintype "bidirectional"))
      (node (ref "R4") (pin "1") (pinfunction "1_1") (pintype "passive"))
    )
    (net (code "45") (name "Net-(U1-PA00{slash}EINT0{slash}SERCOM1.0)") (class "Default")
      (node (ref "C8") (pin "1") (pinfunction "1_1") (pintype "passive"))
      (node (ref "U1") (pin "1") (pinfunction "PA00/EINT0/SERCOM1.0_1") (pintype "bidirectional"))
      (node (ref "X2") (pin "P$1") (pinfunction "P$1_P$1") (pintype "bidirectional"))
    )
    (net (code "46") (name "Net-(U1-PA01{slash}EINT1{slash}SERCOM1.1)") (class "Default")
      (node (ref "C10") (pin "1") (pinfunction "1_1") (pintype "passive"))
      (node (ref "U1") (pin "2") (pinfunction "PA01/EINT1/SERCOM1.1_2") (pintype "bidirectional"))
      (node (ref "X2") (pin "P$2") (pinfunction "P$2_P$2") (pintype "bidirectional"))
    )
    (net (code "47") (name "Net-(U1-PA17{slash}I2C{slash}I1{slash}SERCOM1+3.1)") (class "Default")
      (node (ref "R3") (pin "1") (pinfunction "1_1") (pintype "passive"))
      (node (ref "U1") (pin "26") (pinfunction "PA17/I2C/I1/SERCOM1+3.1_26") (pintype "bidirectional"))
    )
    (net (code "48") (name "Net-(U1-PA30{slash}I10{slash}SECOM1.2{slash}SWCLK)") (class "Default")
      (node (ref "J10") (pin "1") (pinfunction "1_1") (pintype "passive"))
      (node (ref "R24") (pin "1") (pinfunction "1_1") (pintype "passive"))
      (node (ref "U1") (pin "45") (pinfunction "PA30/I10/SECOM1.2/SWCLK_45") (pintype "bidirectional"))
    )
    (net (code "49") (name "Net-(U1-PA31{slash}I11{slash}SECOM1.3{slash}SWDIO)") (class "Default")
      (node (ref "J10") (pin "2") (pinfunction "2_2") (pintype "passive"))
      (node (ref "U1") (pin "46") (pinfunction "PA31/I11/SECOM1.3/SWDIO_46") (pintype "bidirectional"))
    )
    (net (code "50") (name "Net-(U1-VDDCORE)") (class "Default")
      (node (ref "C5") (pin "1") (pinfunction "1_1") (pintype "passive"))
      (node (ref "U1") (pin "43") (pinfunction "VDDCORE_43") (pintype "bidirectional"))
    )
    (net (code "51") (name "Net-(U1-~{RESET})") (class "Default")
      (node (ref "C6") (pin "1") (pinfunction "1_1") (pintype "passive"))
      (node (ref "S1") (pin "1") (pinfunction "1_1") (pintype "passive"))
      (node (ref "S1") (pin "2") (pinfunction "1_2") (pintype "passive"))
      (node (ref "U1") (pin "40") (pinfunction "~{RESET}_40") (pintype "bidirectional"))
    )
    (net (code "52") (name "Net-(U2-1D+)") (class "Default")
      (node (ref "J7") (pin "3") (pinfunction "3_3") (pintype "input"))
      (node (ref "U2") (pin "1") (pinfunction "1D+_1") (pintype "bidirectional"))
    )
    (net (code "53") (name "Net-(U2-1D-)") (class "Default")
      (node (ref "J7") (pin "2") (pinfunction "2_2") (pintype "input"))
      (node (ref "U2") (pin "2") (pinfunction "1D-_2") (pintype "bidirectional"))
    )
    (net (code "54") (name "Net-(U2-S)") (class "Default")
      (node (ref "R1") (pin "2") (pinfunction "2_2") (pintype "passive"))
      (node (ref "R2") (pin "2") (pinfunction "2_2") (pintype "passive"))
      (node (ref "S2") (pin "1") (pinfunction "1_1") (pintype "passive"))
      (node (ref "U2") (pin "9") (pinfunction "S_9") (pintype "bidirectional"))
    )
    (net (code "55") (name "Net-(U3-FB)") (class "Default")
      (node (ref "R13") (pin "1") (pinfunction "1_1") (pintype "passive"))
      (node (ref "R14") (pin "2") (pinfunction "2_2") (pintype "passive"))
      (node (ref "U3") (pin "3") (pinfunction "FB_3") (pintype "bidirectional"))
    )
    (net (code "56") (name "Net-(U3-SW)") (class "Default")
      (node (ref "D4") (pin "A") (pinfunction "A_A") (pintype "passive"))
      (node (ref "L1") (pin "2") (pinfunction "2_2") (pintype "passive"))
      (node (ref "U3") (pin "1") (pinfunction "SW_1") (pintype "bidirectional"))
    )
    (net (code "57") (name "Net-(U4-PG)") (class "Default")
      (node (ref "R23") (pin "1") (pinfunction "1_1") (pintype "passive"))
      (node (ref "U4") (pin "7") (pinfunction "PG_7") (pintype "bidirectional"))
    )
    (net (code "58") (name "Net-(U4-PROG)") (class "Default")
      (node (ref "R20") (pin "2") (pinfunction "2_2") (pintype "passive"))
      (node (ref "U4") (pin "6") (pinfunction "PROG_6") (pintype "bidirectional"))
    )
    (net (code "59") (name "Net-(U4-STAT1)") (class "Default")
      (node (ref "R18") (pin "1") (pinfunction "1_1") (pintype "passive"))
      (node (ref "U4") (pin "3") (pinfunction "STAT1_3") (pintype "bidirectional"))
    )
    (net (code "60") (name "Net-(U4-STAT2)") (class "Default")
      (node (ref "R17") (pin "1") (pinfunction "1_1") (pintype "passive"))
      (node (ref "U4") (pin "4") (pinfunction "STAT2_4") (pintype "bidirectional"))
    )
    (net (code "61") (name "Net-(U4-THERM)") (class "Default")
      (node (ref "R22") (pin "2") (pinfunction "2_2") (pintype "passive"))
      (node (ref "U4") (pin "8") (pinfunction "THERM_8") (pintype "bidirectional"))
    )
    (net (code "62") (name "Net-(U5-EN)") (class "Default")
      (node (ref "R19") (pin "1") (pinfunction "1_1") (pintype "passive"))
      (node (ref "U5") (pin "3") (pinfunction "EN_3") (pintype "bidirectional"))
    )
    (net (code "63") (name "Net-(X3-GPIO15)") (class "Default")
      (node (ref "R7") (pin "2") (pinfunction "2_2") (pintype "passive"))
      (node (ref "X3") (pin "J26") (pinfunction "GPIO15_J26") (pintype "bidirectional"))
    )
    (net (code "64") (name "Net-(X3-GPIO16)") (class "Default")
      (node (ref "R6") (pin "1") (pinfunction "1_1") (pintype "passive"))
      (node (ref "X3") (pin "J27") (pinfunction "GPIO16_J27") (pintype "bidirectional"))
    )
    (net (code "65") (name "SCK") (class "Default")
      (node (ref "J2") (pin "5") (pinfunction "SCLK_5") (pintype "bidirectional"))
      (node (ref "U1") (pin "20") (pinfunction "PB11/I11/SERCOM4.3/I2SCL_20") (pintype "bidirectional"))
      (node (ref "X3") (pin "J18") (pinfunction "SCK_J18") (pintype "input"))
    )
    (net (code "66") (name "SD-~{CD}") (class "Default")
      (node (ref "J2") (pin "CD1") (pinfunction "CARD_DETECT_CD1") (pintype "bidirectional"))
      (node (ref "U1") (pin "16") (pinfunction "PA11/I11/AIN19/SERCOM0+2.3/I2SF0_16") (pintype "bidirectional"))
    )
    (net (code "67") (name "SD-~{CS}") (class "Default")
      (node (ref "J2") (pin "2") (pinfunction "CS_2") (pintype "bidirectional"))
      (node (ref "U1") (pin "27") (pinfunction "PA18/I2/SERCOM1+3.2_27") (pintype "bidirectional"))
    )
    (net (code "68") (name "USB-HOST-EN") (class "Default")
      (node (ref "R1") (pin "1") (pinfunction "1_1") (pintype "passive"))
      (node (ref "U1") (pin "41") (pinfunction "PA28/I8_41") (pintype "bidirectional"))
    )
    (net (code "69") (name "VBATT") (class "Default")
      (node (ref "C26") (pin "1") (pinfunction "1_1") (pintype "passive"))
      (node (ref "C30") (pin "1") (pinfunction "1_1") (pintype "passive"))
      (node (ref "J4") (pin "4") (pinfunction "4_4") (pintype "passive"))
      (node (ref "J6") (pin "2") (pinfunction "2_2") (pintype "bidirectional"))
      (node (ref "L1") (pin "1") (pinfunction "1_1") (pintype "passive"))
      (node (ref "R11") (pin "1") (pinfunction "1_1") (pintype "passive"))
      (node (ref "R15") (pin "1") (pinfunction "1_1") (pintype "passive"))
      (node (ref "R19") (pin "2") (pinfunction "2_2") (pintype "passive"))
      (node (ref "R21") (pin "2") (pinfunction "2_2") (pintype "passive"))
      (node (ref "U3") (pin "4") (pinfunction "EN_4") (pintype "bidirectional"))
      (node (ref "U3") (pin "5") (pinfunction "VIN_5") (pintype "bidirectional"))
      (node (ref "U5") (pin "1") (pinfunction "VIN_1") (pintype "bidirectional"))
    )
    (net (code "70") (name "VBUS") (class "Default")
      (node (ref "F1") (pin "2") (pinfunction "2_2") (pintype "bidirectional"))
      (node (ref "J1") (pin "1") (pinfunction "+5V_1") (pintype "bidirectional"))
      (node (ref "J4") (pin "6") (pinfunction "6_6") (pintype "passive"))
      (node (ref "R12") (pin "1") (pinfunction "1_1") (pintype "passive"))
    )
    (net (code "71") (name "WIFI-CHIP-EN") (class "Default")
      (node (ref "R5") (pin "1") (pinfunction "1_1") (pintype "passive"))
      (node (ref "U1") (pin "12") (pinfunction "PA07/I7/AIN7/SERCOM0.3/I2SD0_12") (pintype "bidirectional"))
      (node (ref "X3") (pin "J22") (pinfunction "CHIP_EN_J22") (pintype "bidirectional"))
    )
    (net (code "72") (name "WIFI-WAKE") (class "Default")
      (node (ref "U1") (pin "15") (pinfunction "PA10/I10/AIN18/SERCOM0+2.2/I2SCK_15") (pintype "bidirectional"))
      (node (ref "X3") (pin "J11") (pinfunction "WAKE_J11") (pintype "bidirectional"))
    )
    (net (code "73") (name "WIFI-~{CS}") (class "Default")
      (node (ref "U1") (pin "11") (pinfunction "PA06/EINT6/AIN6/SERCOM0.2_11") (pintype "bidirectional"))
      (node (ref "X3") (pin "J16") (pinfunction "CS_J16") (pintype "input"))
    )
    (net (code "74") (name "WIFI-~{IRQ}") (class "Default")
      (node (ref "U1") (pin "14") (pinfunction "PA09/I2C/I9/AIN17/SERCOM0+2.1/I2SMC_14") (pintype "bidirectional"))
      (node (ref "X3") (pin "J13") (pinfunction "~{IRQ}_J13") (pintype "bidirectional"))
    )
    (net (code "75") (name "WIFI-~{RESET}") (class "Default")
      (node (ref "R8") (pin "2") (pinfunction "2_2") (pintype "passive"))
      (node (ref "U1") (pin "13") (pinfunction "PA08/I2C/AIN16/SERCOM0+2.0/I2SD1_13") (pintype "bidirectional"))
      (node (ref "X3") (pin "J4") (pinfunction "~{RESET}_J4") (pintype "input"))
    )
    (net (code "76") (name "unconnected-(J2-CARD_DETECT1-PadCD2)") (class "Default")
      (node (ref "J2") (pin "CD2") (pinfunction "CARD_DETECT1_CD2") (pintype "bidirectional"))
    )
    (net (code "77") (name "unconnected-(J2-DAT1-Pad8)") (class "Default")
      (node (ref "J2") (pin "8") (pinfunction "DAT1_8") (pintype "bidirectional"))
    )
    (net (code "78") (name "unconnected-(J2-DAT2-Pad1)") (class "Default")
      (node (ref "J2") (pin "1") (pinfunction "DAT2_1") (pintype "bidirectional"))
    )
    (net (code "79") (name "unconnected-(J3-Pad28)") (class "Default")
      (node (ref "J3") (pin "28") (pinfunction "28_28") (pintype "bidirectional"))
    )
    (net (code "80") (name "unconnected-(J4-Pad2)") (class "Default")
      (node (ref "J4") (pin "2") (pinfunction "2_2") (pintype "passive"))
    )
    (net (code "81") (name "unconnected-(J7-Pad4)") (class "Default")
      (node (ref "J7") (pin "4") (pinfunction "4_4") (pintype "input"))
    )
    (net (code "82") (name "unconnected-(S3-1B-Pad2)") (class "Default")
      (node (ref "S3") (pin "2") (pinfunction "1B_2") (pintype "passive"))
    )
    (net (code "83") (name "unconnected-(S4-1B-Pad2)") (class "Default")
      (node (ref "S4") (pin "2") (pinfunction "1B_2") (pintype "passive"))
    )
    (net (code "84") (name "unconnected-(S5-1B-Pad2)") (class "Default")
      (node (ref "S5") (pin "2") (pinfunction "1B_2") (pintype "passive"))
    )
    (net (code "85") (name "unconnected-(S6-1A-Pad1)") (class "Default")
      (node (ref "S6") (pin "1") (pinfunction "1A_1") (pintype "passive"))
    )
    (net (code "86") (name "unconnected-(U1-PA03{slash}EINT3{slash}VREFA{slash}AIN1-Pad4)") (class "Default")
      (node (ref "U1") (pin "4") (pinfunction "PA03/EINT3/VREFA/AIN1_4") (pintype "bidirectional"))
    )
    (net (code "87") (name "unconnected-(U1-PA13{slash}I13{slash}I2C{slash}SERCOM2+4.1-Pad22)") (class "Default")
      (node (ref "U1") (pin "22") (pinfunction "PA13/I13/I2C/SERCOM2+4.1_22") (pintype "bidirectional"))
    )
    (net (code "88") (name "unconnected-(U1-PA19{slash}I3{slash}SERCOM1+3.3{slash}I2SD0-Pad28)") (class "Default")
      (node (ref "U1") (pin "28") (pinfunction "PA19/I3/SERCOM1+3.3/I2SD0_28") (pintype "bidirectional"))
    )
    (net (code "89") (name "unconnected-(U1-PA20{slash}I4{slash}SERCOM3+5.2{slash}I2SSC-Pad29)") (class "Default")
      (node (ref "U1") (pin "29") (pinfunction "PA20/I4/SERCOM3+5.2/I2SSC_29") (pintype "bidirectional"))
    )
    (net (code "90") (name "unconnected-(U1-PA21{slash}I5{slash}SERCOM3+5.3{slash}I2SFS0-Pad30)") (class "Default")
      (node (ref "U1") (pin "30") (pinfunction "PA21/I5/SERCOM3+5.3/I2SFS0_30") (pintype "bidirectional"))
    )
    (net (code "91") (name "unconnected-(U1-PA22{slash}I2C{slash}I6{slash}SERCOM3+5.0-Pad31)") (class "Default")
      (node (ref "U1") (pin "31") (pinfunction "PA22/I2C/I6/SERCOM3+5.0_31") (pintype "bidirectional"))
    )
    (net (code "92") (name "unconnected-(U1-PA23{slash}I2C{slash}I7{slash}SERCOM3+5.1{slash}SOF-Pad32)") (class "Default")
      (node (ref "U1") (pin "32") (pinfunction "PA23/I2C/I7/SERCOM3+5.1/SOF_32") (pintype "bidirectional"))
    )
    (net (code "93") (name "unconnected-(U1-PA27{slash}I15-Pad39)") (class "Default")
      (node (ref "U1") (pin "39") (pinfunction "PA27/I15_39") (pintype "bidirectional"))
    )
    (net (code "94") (name "unconnected-(U1-PB02{slash}I2{slash}AIN10{slash}SERCOM5.0-Pad47)") (class "Default")
      (node (ref "U1") (pin "47") (pinfunction "PB02/I2/AIN10/SERCOM5.0_47") (pintype "bidirectional"))
    )
    (net (code "95") (name "unconnected-(U1-PB03{slash}I3{slash}AIN11{slash}SERCOM5.1-Pad48)") (class "Default")
      (node (ref "U1") (pin "48") (pinfunction "PB03/I3/AIN11/SERCOM5.1_48") (pintype "bidirectional"))
    )
    (net (code "96") (name "unconnected-(X3-1.3V-PadJ24)") (class "Default")
      (node (ref "X3") (pin "J24") (pinfunction "1.3V_J24") (pintype "bidirectional"))
    )
    (net (code "97") (name "unconnected-(X3-GPIO1-PadJ21)") (class "Default")
      (node (ref "X3") (pin "J21") (pinfunction "GPIO1_J21") (pintype "bidirectional"))
    )
    (net (code "98") (name "unconnected-(X3-GPIO18-PadJ1)") (class "Default")
      (node (ref "X3") (pin "J1") (pinfunction "GPIO18_J1") (pintype "bidirectional"))
    )
    (net (code "99") (name "unconnected-(X3-RXD-PadJ19)") (class "Default")
      (node (ref "X3") (pin "J19") (pinfunction "RXD_J19") (pintype "input"))
    )
    (net (code "100") (name "unconnected-(X3-SCL-PadJ2)") (class "Default")
      (node (ref "X3") (pin "J2") (pinfunction "SCL_J2") (pintype "bidirectional"))
    )
    (net (code "101") (name "unconnected-(X3-SDA-PadJ3)") (class "Default")
      (node (ref "X3") (pin "J3") (pinfunction "SDA_J3") (pintype "bidirectional"))
    )
    (net (code "102") (name "unconnected-(X3-TXD-PadJ14)") (class "Default")
      (node (ref "X3") (pin "J14") (pinfunction "TXD_J14") (pintype "bidirectional"))
    )
  )
)
